# NRF24-breakout.net
KiCad netlist of a schematic drawn in EAGLE
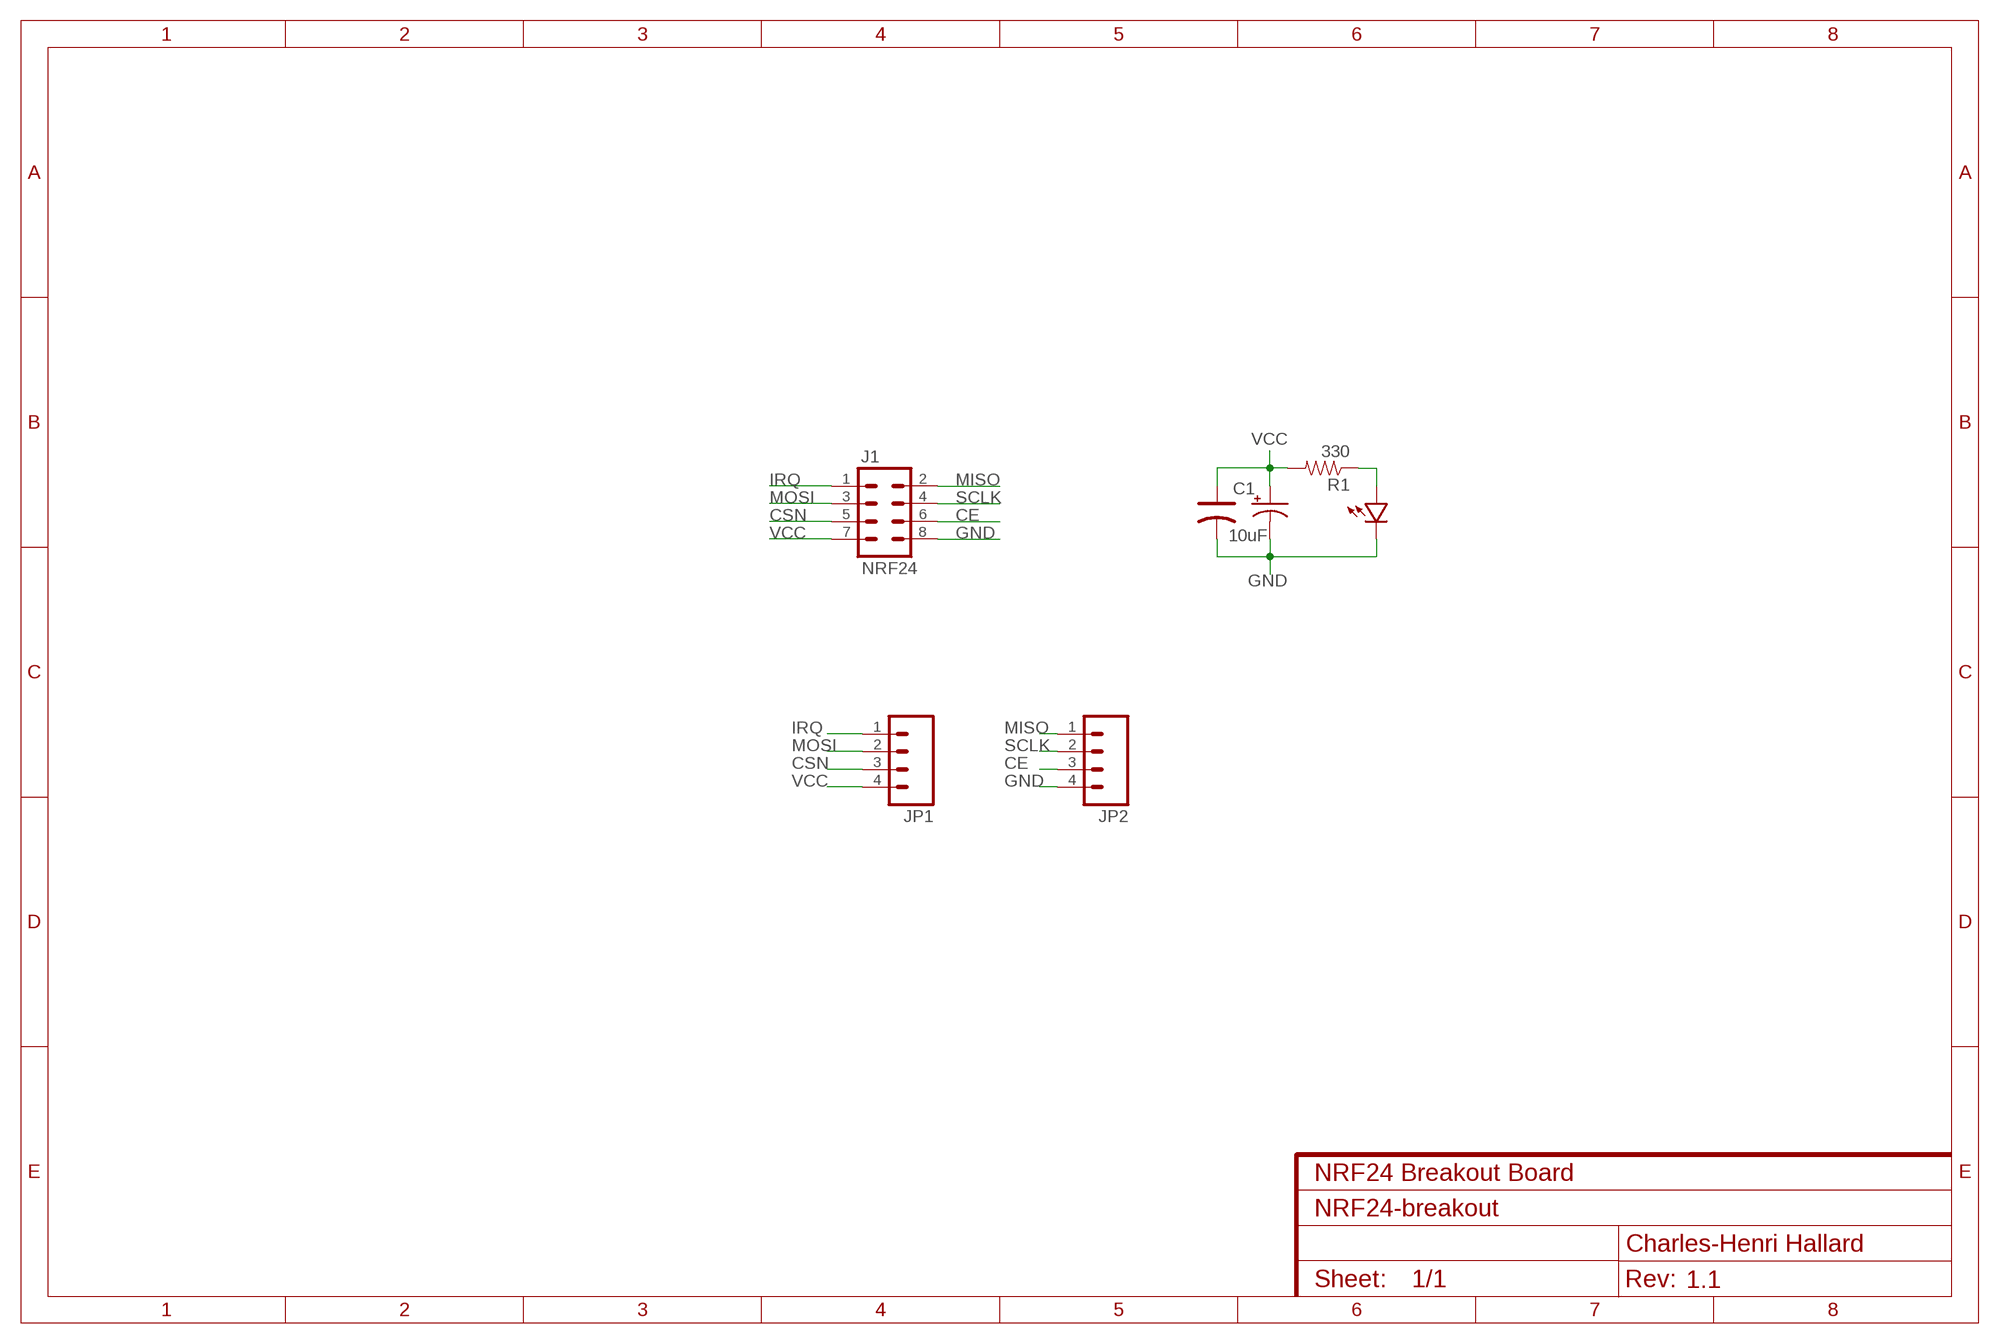
[diagram p0: schematic, sheet 1]

(export (version "E")
  (design (tool "Eeschema 10.0.6"))
  (components
    (comp (ref "C1")
      (value "10uF")
      (footprint "eagle-import:B45181A")
      (libsource (lib "eagle-import") (part "CPOL-USB45181A"))
    )
    (comp (ref "C3")
      (value "CAP-POLAR-1210")
      (footprint "eagle-import:1210")
      (libsource (lib "eagle-import") (part "CAP-POLAR-1210"))
    )
    (comp (ref "J1")
      (value "NRF24")
      (footprint "eagle-import:2X4")
      (libsource (lib "eagle-import") (part "M04X2"))
    )
    (comp (ref "JP1")
      (value "M04PTH")
      (footprint "eagle-import:1X04")
      (libsource (lib "eagle-import") (part "M04PTH"))
    )
    (comp (ref "JP2")
      (value "M04PTH")
      (footprint "eagle-import:1X04")
      (libsource (lib "eagle-import") (part "M04PTH"))
    )
    (comp (ref "R1")
      (value "330")
      (footprint "eagle-import:0805-RES")
      (libsource (lib "eagle-import") (part "RESISTOR0805-RES"))
    )
    (comp (ref "U$1")
      (value "LED0805-LARGE")
      (footprint "eagle-import:0805-LED-LARGEPADS")
      (libsource (lib "eagle-import") (part "LED0805-LARGE"))
    )
  )
  (nets
    (net (code "1") (name "/CE") (class "Default")
      (node (ref "J1") (pin "6") (pinfunction "6_6") (pintype "passive"))
      (node (ref "JP2") (pin "3") (pinfunction "3_3") (pintype "passive"))
    )
    (net (code "2") (name "/CSN") (class "Default")
      (node (ref "J1") (pin "5") (pinfunction "5_5") (pintype "passive"))
      (node (ref "JP1") (pin "3") (pinfunction "3_3") (pintype "passive"))
    )
    (net (code "3") (name "/GND") (class "Default")
      (node (ref "C1") (pin "-") (pinfunction "-_-") (pintype "passive"))
      (node (ref "C3") (pin "-") (pinfunction "-_-") (pintype "passive"))
      (node (ref "J1") (pin "8") (pinfunction "8_8") (pintype "passive"))
      (node (ref "JP2") (pin "4") (pinfunction "4_4") (pintype "passive"))
      (node (ref "U$1") (pin "MINUS") (pinfunction "MINUS_MINUS") (pintype "passive"))
    )
    (net (code "4") (name "/IRQ") (class "Default")
      (node (ref "J1") (pin "1") (pinfunction "1_1") (pintype "passive"))
      (node (ref "JP1") (pin "1") (pinfunction "1_1") (pintype "passive"))
    )
    (net (code "5") (name "/MISO") (class "Default")
      (node (ref "J1") (pin "2") (pinfunction "2_2") (pintype "passive"))
      (node (ref "JP2") (pin "1") (pinfunction "1_1") (pintype "passive"))
    )
    (net (code "6") (name "/MOSI") (class "Default")
      (node (ref "J1") (pin "3") (pinfunction "3_3") (pintype "passive"))
      (node (ref "JP1") (pin "2") (pinfunction "2_2") (pintype "passive"))
    )
    (net (code "7") (name "/SCLK") (class "Default")
      (node (ref "J1") (pin "4") (pinfunction "4_4") (pintype "passive"))
      (node (ref "JP2") (pin "2") (pinfunction "2_2") (pintype "passive"))
    )
    (net (code "8") (name "/VCC") (class "Default")
      (node (ref "C1") (pin "+") (pinfunction "+_+") (pintype "passive"))
      (node (ref "C3") (pin "+") (pinfunction "+_+") (pintype "passive"))
      (node (ref "J1") (pin "7") (pinfunction "7_7") (pintype "passive"))
      (node (ref "JP1") (pin "4") (pinfunction "4_4") (pintype "passive"))
      (node (ref "R1") (pin "2") (pinfunction "2_2") (pintype "passive"))
    )
    (net (code "9") (name "Net-(R1-Pad1)") (class "Default")
      (node (ref "R1") (pin "1") (pinfunction "1_1") (pintype "passive"))
      (node (ref "U$1") (pin "PLUS") (pinfunction "PLUS_PLUS") (pintype "passive"))
    )
  )
)
